# Sheet2.net
KiCad netlist of a schematic drawn in Altium Designer
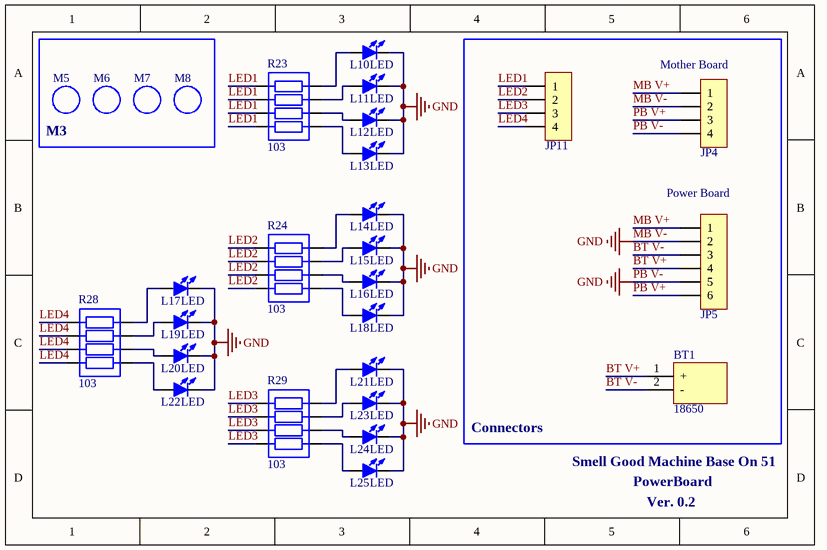
[diagram p0: Sheet2.SchDoc]

(export (version "E")
  (design (tool "Eeschema 10.0.6"))
  (components
    (comp (ref "BT1")
      (value "18650")
      (footprint "18650_battery")
      (description "Battery")
      (libsource (lib "10 - 未分类元器件") (part "18650"))
    )
    (comp (ref "JP4")
      (value "HDR-1X4")
      (footprint "HDR2.54-M-LI-4P")
      (description "4P接插件")
      (libsource (lib "17 - 接插件-脚距2.54mm (100mil) ") (part "Header 4"))
    )
    (comp (ref "JP5")
      (value "HDR-1X6")
      (footprint "HDR2.54-M-LI-6P")
      (description "6P接插件")
      (libsource (lib "17 - 接插件-脚距2.54mm (100mil) ") (part "Header 6"))
    )
    (comp (ref "JP11")
      (value "HDR-1X4")
      (footprint "HDR2.54-LI-4P")
      (description "4P接插件")
      (libsource (lib "17 - 接插件-脚距2.54mm (100mil) ") (part "Header 4"))
    )
    (comp (ref "L10")
      (value "LED")
      (footprint "LED 0805G")
      (description "发光二极管")
      (libsource (lib "02 - 二极管(LED)-三极管-整流桥") (part "LED"))
    )
    (comp (ref "L11")
      (value "LED")
      (footprint "LED 0805G")
      (description "发光二极管")
      (libsource (lib "02 - 二极管(LED)-三极管-整流桥") (part "LED"))
    )
    (comp (ref "L12")
      (value "LED")
      (footprint "LED 0805G")
      (description "发光二极管")
      (libsource (lib "02 - 二极管(LED)-三极管-整流桥") (part "LED"))
    )
    (comp (ref "L13")
      (value "LED")
      (footprint "LED 0805G")
      (description "发光二极管")
      (libsource (lib "02 - 二极管(LED)-三极管-整流桥") (part "LED"))
    )
    (comp (ref "L14")
      (value "LED")
      (footprint "LED 0805G")
      (description "发光二极管")
      (libsource (lib "02 - 二极管(LED)-三极管-整流桥") (part "LED"))
    )
    (comp (ref "L15")
      (value "LED")
      (footprint "LED 0805G")
      (description "发光二极管")
      (libsource (lib "02 - 二极管(LED)-三极管-整流桥") (part "LED"))
    )
    (comp (ref "L16")
      (value "LED")
      (footprint "LED 0805G")
      (description "发光二极管")
      (libsource (lib "02 - 二极管(LED)-三极管-整流桥") (part "LED"))
    )
    (comp (ref "L17")
      (value "LED")
      (footprint "LED 0805G")
      (description "发光二极管")
      (libsource (lib "02 - 二极管(LED)-三极管-整流桥") (part "LED"))
    )
    (comp (ref "L18")
      (value "LED")
      (footprint "LED 0805G")
      (description "发光二极管")
      (libsource (lib "02 - 二极管(LED)-三极管-整流桥") (part "LED"))
    )
    (comp (ref "L19")
      (value "LED")
      (footprint "LED 0805G")
      (description "发光二极管")
      (libsource (lib "02 - 二极管(LED)-三极管-整流桥") (part "LED"))
    )
    (comp (ref "L20")
      (value "LED")
      (footprint "LED 0805G")
      (description "发光二极管")
      (libsource (lib "02 - 二极管(LED)-三极管-整流桥") (part "LED"))
    )
    (comp (ref "L21")
      (value "LED")
      (footprint "LED 0805G")
      (description "发光二极管")
      (libsource (lib "02 - 二极管(LED)-三极管-整流桥") (part "LED"))
    )
    (comp (ref "L22")
      (value "LED")
      (footprint "LED 0805G")
      (description "发光二极管")
      (libsource (lib "02 - 二极管(LED)-三极管-整流桥") (part "LED"))
    )
    (comp (ref "L23")
      (value "LED")
      (footprint "LED 0805G")
      (description "发光二极管")
      (libsource (lib "02 - 二极管(LED)-三极管-整流桥") (part "LED"))
    )
    (comp (ref "L24")
      (value "LED")
      (footprint "LED 0805G")
      (description "发光二极管")
      (libsource (lib "02 - 二极管(LED)-三极管-整流桥") (part "LED"))
    )
    (comp (ref "L25")
      (value "LED")
      (footprint "LED 0805G")
      (description "发光二极管")
      (libsource (lib "02 - 二极管(LED)-三极管-整流桥") (part "LED"))
    )
    (comp (ref "M5")
      (value "M3")
      (footprint "M3x20_N")
      (description "铜柱孔")
      (libsource (lib "10 - 未分类元器件") (part "M3"))
    )
    (comp (ref "M6")
      (value "M3")
      (footprint "M3x20_N")
      (description "铜柱孔")
      (libsource (lib "10 - 未分类元器件") (part "M3"))
    )
    (comp (ref "M7")
      (value "M3")
      (footprint "M3x20_N")
      (description "铜柱孔")
      (libsource (lib "10 - 未分类元器件") (part "M3"))
    )
    (comp (ref "M8")
      (value "M3")
      (footprint "M3x20_N")
      (description "铜柱孔")
      (libsource (lib "10 - 未分类元器件") (part "M3"))
    )
    (comp (ref "R23")
      (value "103")
      (footprint "RCA-8P4R-0603")
      (description "贴片排阻")
      (libsource (lib "01 - 电容-电阻-电感") (part "R-8P4R"))
    )
    (comp (ref "R24")
      (value "103")
      (footprint "RCA-8P4R-0603")
      (description "贴片排阻")
      (libsource (lib "01 - 电容-电阻-电感") (part "R-8P4R"))
    )
    (comp (ref "R28")
      (value "103")
      (footprint "RCA-8P4R-0603")
      (description "贴片排阻")
      (libsource (lib "01 - 电容-电阻-电感") (part "R-8P4R"))
    )
    (comp (ref "R29")
      (value "103")
      (footprint "RCA-8P4R-0603")
      (description "贴片排阻")
      (libsource (lib "01 - 电容-电阻-电感") (part "R-8P4R"))
    )
  )
  (nets
    (net (code "1") (name "/BT V+") (class "Default")
      (node (ref "BT1") (pin "1") (pinfunction "+_1") (pintype "passive"))
      (node (ref "JP5") (pin "4") (pinfunction "4_4") (pintype "passive"))
    )
    (net (code "2") (name "/BT V-") (class "Default")
      (node (ref "BT1") (pin "2") (pinfunction "-_2") (pintype "passive"))
      (node (ref "JP5") (pin "3") (pinfunction "3_3") (pintype "passive"))
    )
    (net (code "3") (name "/LED1") (class "Default")
      (node (ref "JP11") (pin "1") (pinfunction "1_1") (pintype "passive"))
      (node (ref "R23") (pin "1") (pinfunction "1_1") (pintype "passive"))
      (node (ref "R23") (pin "2") (pinfunction "2_2") (pintype "passive"))
      (node (ref "R23") (pin "3") (pinfunction "3_3") (pintype "passive"))
      (node (ref "R23") (pin "4") (pinfunction "4_4") (pintype "passive"))
    )
    (net (code "4") (name "/LED2") (class "Default")
      (node (ref "JP11") (pin "2") (pinfunction "2_2") (pintype "passive"))
      (node (ref "R24") (pin "1") (pinfunction "1_1") (pintype "passive"))
      (node (ref "R24") (pin "2") (pinfunction "2_2") (pintype "passive"))
      (node (ref "R24") (pin "3") (pinfunction "3_3") (pintype "passive"))
      (node (ref "R24") (pin "4") (pinfunction "4_4") (pintype "passive"))
    )
    (net (code "5") (name "/LED3") (class "Default")
      (node (ref "JP11") (pin "3") (pinfunction "3_3") (pintype "passive"))
      (node (ref "R29") (pin "1") (pinfunction "1_1") (pintype "passive"))
      (node (ref "R29") (pin "2") (pinfunction "2_2") (pintype "passive"))
      (node (ref "R29") (pin "3") (pinfunction "3_3") (pintype "passive"))
      (node (ref "R29") (pin "4") (pinfunction "4_4") (pintype "passive"))
    )
    (net (code "6") (name "/LED4") (class "Default")
      (node (ref "JP11") (pin "4") (pinfunction "4_4") (pintype "passive"))
      (node (ref "R28") (pin "1") (pinfunction "1_1") (pintype "passive"))
      (node (ref "R28") (pin "2") (pinfunction "2_2") (pintype "passive"))
      (node (ref "R28") (pin "3") (pinfunction "3_3") (pintype "passive"))
      (node (ref "R28") (pin "4") (pinfunction "4_4") (pintype "passive"))
    )
    (net (code "7") (name "/MB V+") (class "Default")
      (node (ref "JP4") (pin "1") (pinfunction "1_1") (pintype "passive"))
      (node (ref "JP5") (pin "1") (pinfunction "1_1") (pintype "passive"))
    )
    (net (code "8") (name "/PB V+") (class "Default")
      (node (ref "JP4") (pin "3") (pinfunction "3_3") (pintype "passive"))
      (node (ref "JP5") (pin "6") (pinfunction "6_6") (pintype "passive"))
    )
    (net (code "9") (name "GND") (class "Default")
      (node (ref "JP4") (pin "2") (pinfunction "2_2") (pintype "passive"))
      (node (ref "JP4") (pin "4") (pinfunction "4_4") (pintype "passive"))
      (node (ref "JP5") (pin "2") (pinfunction "2_2") (pintype "passive"))
      (node (ref "JP5") (pin "5") (pinfunction "5_5") (pintype "passive"))
      (node (ref "L10") (pin "2") (pinfunction "K_2") (pintype "passive"))
      (node (ref "L11") (pin "2") (pinfunction "K_2") (pintype "passive"))
      (node (ref "L12") (pin "2") (pinfunction "K_2") (pintype "passive"))
      (node (ref "L13") (pin "2") (pinfunction "K_2") (pintype "passive"))
      (node (ref "L14") (pin "2") (pinfunction "K_2") (pintype "passive"))
      (node (ref "L15") (pin "2") (pinfunction "K_2") (pintype "passive"))
      (node (ref "L16") (pin "2") (pinfunction "K_2") (pintype "passive"))
      (node (ref "L17") (pin "2") (pinfunction "K_2") (pintype "passive"))
      (node (ref "L18") (pin "2") (pinfunction "K_2") (pintype "passive"))
      (node (ref "L19") (pin "2") (pinfunction "K_2") (pintype "passive"))
      (node (ref "L20") (pin "2") (pinfunction "K_2") (pintype "passive"))
      (node (ref "L21") (pin "2") (pinfunction "K_2") (pintype "passive"))
      (node (ref "L22") (pin "2") (pinfunction "K_2") (pintype "passive"))
      (node (ref "L23") (pin "2") (pinfunction "K_2") (pintype "passive"))
      (node (ref "L24") (pin "2") (pinfunction "K_2") (pintype "passive"))
      (node (ref "L25") (pin "2") (pinfunction "K_2") (pintype "passive"))
    )
    (net (code "10") (name "Net-(L10-A)") (class "Default")
      (node (ref "L10") (pin "1") (pinfunction "A_1") (pintype "passive"))
      (node (ref "R23") (pin "8") (pinfunction "8_8") (pintype "passive"))
    )
    (net (code "11") (name "Net-(L11-A)") (class "Default")
      (node (ref "L11") (pin "1") (pinfunction "A_1") (pintype "passive"))
      (node (ref "R23") (pin "7") (pinfunction "7_7") (pintype "passive"))
    )
    (net (code "12") (name "Net-(L12-A)") (class "Default")
      (node (ref "L12") (pin "1") (pinfunction "A_1") (pintype "passive"))
      (node (ref "R23") (pin "6") (pinfunction "6_6") (pintype "passive"))
    )
    (net (code "13") (name "Net-(L13-A)") (class "Default")
      (node (ref "L13") (pin "1") (pinfunction "A_1") (pintype "passive"))
      (node (ref "R23") (pin "5") (pinfunction "5_5") (pintype "passive"))
    )
    (net (code "14") (name "Net-(L14-A)") (class "Default")
      (node (ref "L14") (pin "1") (pinfunction "A_1") (pintype "passive"))
      (node (ref "R24") (pin "8") (pinfunction "8_8") (pintype "passive"))
    )
    (net (code "15") (name "Net-(L15-A)") (class "Default")
      (node (ref "L15") (pin "1") (pinfunction "A_1") (pintype "passive"))
      (node (ref "R24") (pin "7") (pinfunction "7_7") (pintype "passive"))
    )
    (net (code "16") (name "Net-(L16-A)") (class "Default")
      (node (ref "L16") (pin "1") (pinfunction "A_1") (pintype "passive"))
      (node (ref "R24") (pin "6") (pinfunction "6_6") (pintype "passive"))
    )
    (net (code "17") (name "Net-(L17-A)") (class "Default")
      (node (ref "L17") (pin "1") (pinfunction "A_1") (pintype "passive"))
      (node (ref "R28") (pin "8") (pinfunction "8_8") (pintype "passive"))
    )
    (net (code "18") (name "Net-(L18-A)") (class "Default")
      (node (ref "L18") (pin "1") (pinfunction "A_1") (pintype "passive"))
      (node (ref "R24") (pin "5") (pinfunction "5_5") (pintype "passive"))
    )
    (net (code "19") (name "Net-(L19-A)") (class "Default")
      (node (ref "L19") (pin "1") (pinfunction "A_1") (pintype "passive"))
      (node (ref "R28") (pin "7") (pinfunction "7_7") (pintype "passive"))
    )
    (net (code "20") (name "Net-(L20-A)") (class "Default")
      (node (ref "L20") (pin "1") (pinfunction "A_1") (pintype "passive"))
      (node (ref "R28") (pin "6") (pinfunction "6_6") (pintype "passive"))
    )
    (net (code "21") (name "Net-(L21-A)") (class "Default")
      (node (ref "L21") (pin "1") (pinfunction "A_1") (pintype "passive"))
      (node (ref "R29") (pin "8") (pinfunction "8_8") (pintype "passive"))
    )
    (net (code "22") (name "Net-(L22-A)") (class "Default")
      (node (ref "L22") (pin "1") (pinfunction "A_1") (pintype "passive"))
      (node (ref "R28") (pin "5") (pinfunction "5_5") (pintype "passive"))
    )
    (net (code "23") (name "Net-(L23-A)") (class "Default")
      (node (ref "L23") (pin "1") (pinfunction "A_1") (pintype "passive"))
      (node (ref "R29") (pin "7") (pinfunction "7_7") (pintype "passive"))
    )
    (net (code "24") (name "Net-(L24-A)") (class "Default")
      (node (ref "L24") (pin "1") (pinfunction "A_1") (pintype "passive"))
      (node (ref "R29") (pin "6") (pinfunction "6_6") (pintype "passive"))
    )
    (net (code "25") (name "Net-(L25-A)") (class "Default")
      (node (ref "L25") (pin "1") (pinfunction "A_1") (pintype "passive"))
      (node (ref "R29") (pin "5") (pinfunction "5_5") (pintype "passive"))
    )
  )
)
